# Controller.net
KiCad netlist of a schematic drawn in Altium Designer
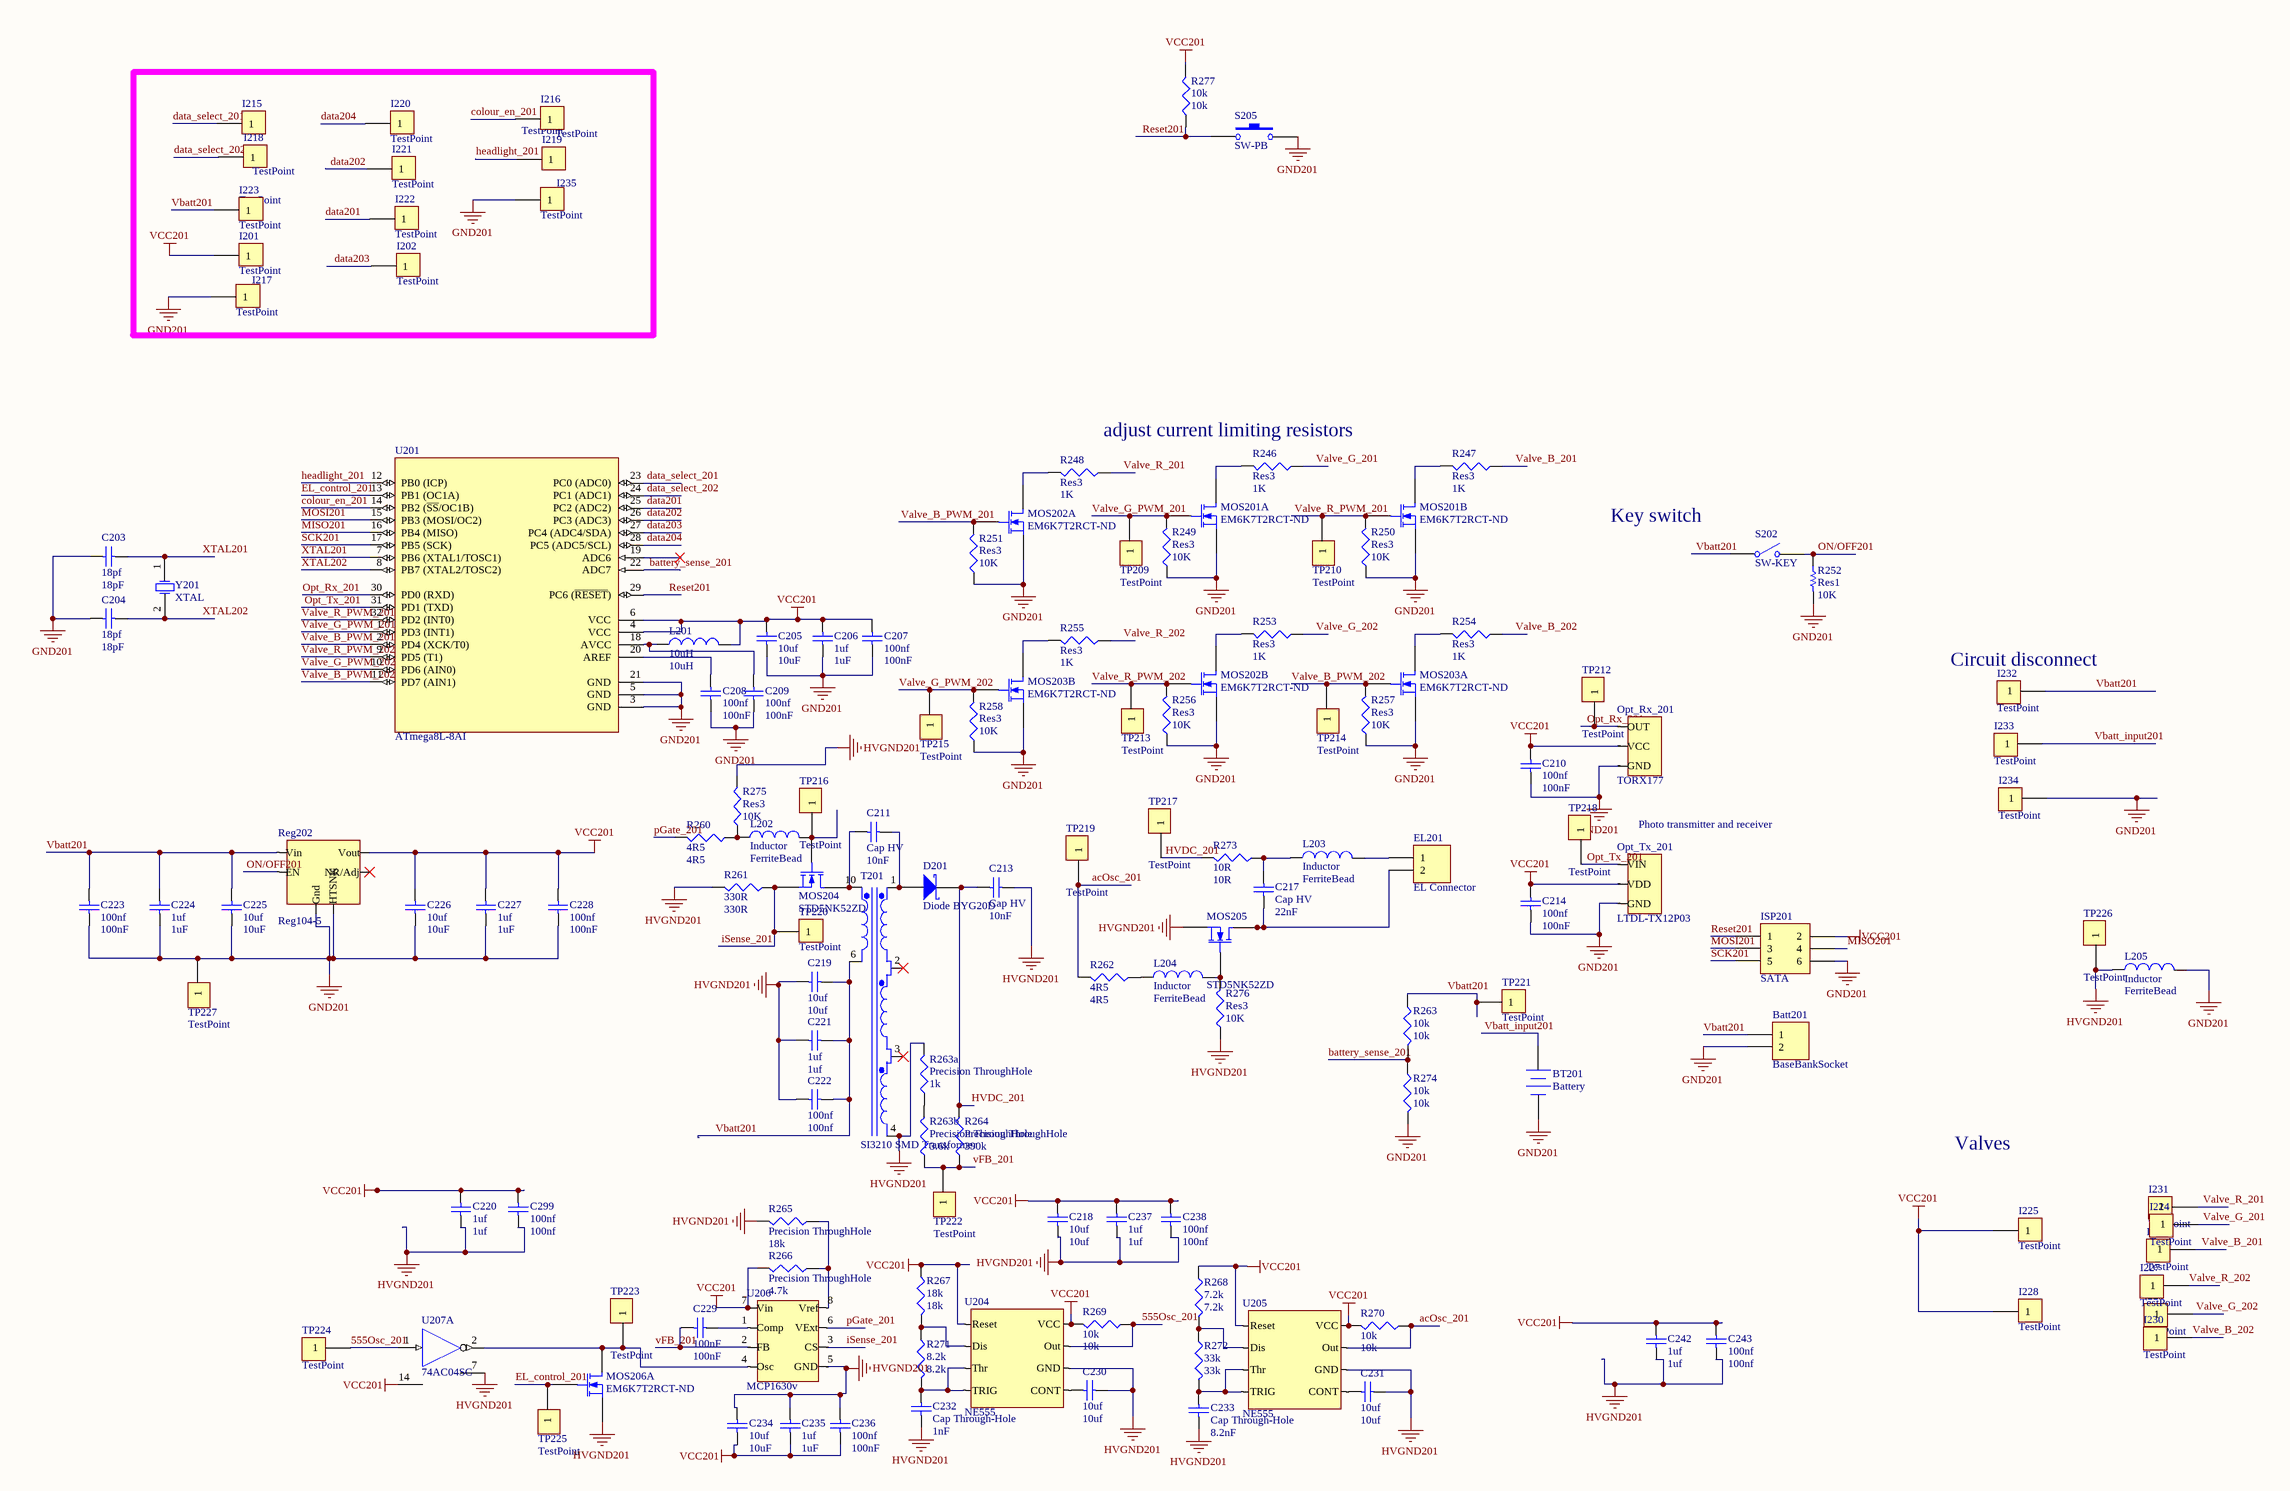
[diagram p0: Controller.SchDoc]

(export (version "E")
  (design (tool "Eeschema 10.0.6"))
  (components
    (comp (ref "Batt201")
      (value "BaseBankSocket")
      (footprint "HDR1X2")
      (description "Header, 2-Pin")
      (libsource (lib "Miscellaneous Connectors") (part "Header 2"))
    )
    (comp (ref "BT201")
      (value "Battery")
      (footprint "BAT-2")
      (description "Multicell Battery")
      (libsource (lib "Miscellaneous Devices") (part "Battery"))
    )
    (comp (ref "C203")
      (value "18pf")
      (footprint "0603")
      (description "Capacitor (Semiconductor SIM Model)")
      (fields (field (name "ALTIUM_VALUE") "18pF"))
      (libsource (lib "Miscellaneous Devices") (part "Cap Semi"))
    )
    (comp (ref "C204")
      (value "18pf")
      (footprint "0603")
      (description "Capacitor (Semiconductor SIM Model)")
      (fields (field (name "ALTIUM_VALUE") "18pF"))
      (libsource (lib "Miscellaneous Devices") (part "Cap Semi"))
    )
    (comp (ref "C205")
      (value "10uf")
      (footprint "0805")
      (description "Capacitor (Semiconductor SIM Model)")
      (fields (field (name "ALTIUM_VALUE") "10uF"))
      (libsource (lib "Miscellaneous Devices") (part "Cap Semi"))
    )
    (comp (ref "C206")
      (value "1uf")
      (footprint "0603")
      (description "Capacitor (Semiconductor SIM Model)")
      (fields (field (name "ALTIUM_VALUE") "1uF"))
      (libsource (lib "Miscellaneous Devices") (part "Cap Semi"))
    )
    (comp (ref "C207")
      (value "100nf")
      (footprint "0603")
      (description "Capacitor (Semiconductor SIM Model)")
      (fields (field (name "ALTIUM_VALUE") "100nF"))
      (libsource (lib "Miscellaneous Devices") (part "Cap Semi"))
    )
    (comp (ref "C208")
      (value "100nf")
      (footprint "0603")
      (description "Capacitor (Semiconductor SIM Model)")
      (fields (field (name "ALTIUM_VALUE") "100nF"))
      (libsource (lib "Miscellaneous Devices") (part "Cap Semi"))
    )
    (comp (ref "C209")
      (value "100nf")
      (footprint "0603")
      (description "Capacitor (Semiconductor SIM Model)")
      (fields (field (name "ALTIUM_VALUE") "100nF"))
      (libsource (lib "Miscellaneous Devices") (part "Cap Semi"))
    )
    (comp (ref "C210")
      (value "100nf")
      (footprint "0603")
      (description "Capacitor (Semiconductor SIM Model)")
      (fields (field (name "ALTIUM_VALUE") "100nF"))
      (libsource (lib "Miscellaneous Devices") (part "Cap Semi"))
    )
    (comp (ref "C211")
      (value "Cap HV")
      (footprint "10n MU Capacitor (HV)")
      (description "Capacitor (Semiconductor SIM Model)")
      (fields (field (name "ALTIUM_VALUE") "10nF"))
      (libsource (lib "Miscellaneous Devices") (part "Cap Semi"))
    )
    (comp (ref "C213")
      (value "Cap HV")
      (footprint "10n MU Capacitor (HV)")
      (description "Capacitor (Semiconductor SIM Model)")
      (fields (field (name "ALTIUM_VALUE") "10nF"))
      (libsource (lib "Miscellaneous Devices") (part "Cap Semi"))
    )
    (comp (ref "C214")
      (value "100nf")
      (footprint "0603")
      (description "Capacitor (Semiconductor SIM Model)")
      (fields (field (name "ALTIUM_VALUE") "100nF"))
      (libsource (lib "Miscellaneous Devices") (part "Cap Semi"))
    )
    (comp (ref "C217")
      (value "Cap HV")
      (footprint "22N MU Capacitor (HV)")
      (description "Capacitor (Semiconductor SIM Model)")
      (fields (field (name "ALTIUM_VALUE") "22nF"))
      (libsource (lib "Miscellaneous Devices") (part "Cap Semi"))
    )
    (comp (ref "C218")
      (value "10uf")
      (footprint "0805")
      (description "Capacitor (Semiconductor SIM Model)")
      (fields (field (name "ALTIUM_VALUE") "10uf"))
      (libsource (lib "Miscellaneous Devices") (part "Cap Semi"))
    )
    (comp (ref "C219")
      (value "10uf")
      (footprint "0805")
      (description "Capacitor (Semiconductor SIM Model)")
      (fields (field (name "ALTIUM_VALUE") "10uf"))
      (libsource (lib "Miscellaneous Devices") (part "Cap Semi"))
    )
    (comp (ref "C220")
      (value "1uf")
      (footprint "0603")
      (description "Capacitor (Semiconductor SIM Model)")
      (fields (field (name "ALTIUM_VALUE") "1uf"))
      (libsource (lib "Miscellaneous Devices") (part "Cap Semi"))
    )
    (comp (ref "C221")
      (value "1uf")
      (footprint "0603")
      (description "Capacitor (Semiconductor SIM Model)")
      (fields (field (name "ALTIUM_VALUE") "1uf"))
      (libsource (lib "Miscellaneous Devices") (part "Cap Semi"))
    )
    (comp (ref "C222")
      (value "100nf")
      (footprint "0603")
      (description "Capacitor (Semiconductor SIM Model)")
      (fields (field (name "ALTIUM_VALUE") "100nf"))
      (libsource (lib "Miscellaneous Devices") (part "Cap Semi"))
    )
    (comp (ref "C223")
      (value "100nf")
      (footprint "0603")
      (description "Capacitor (Semiconductor SIM Model)")
      (fields (field (name "ALTIUM_VALUE") "100nF"))
      (libsource (lib "Miscellaneous Devices") (part "Cap Semi"))
    )
    (comp (ref "C224")
      (value "1uf")
      (footprint "0603")
      (description "Capacitor (Semiconductor SIM Model)")
      (fields (field (name "ALTIUM_VALUE") "1uF"))
      (libsource (lib "Miscellaneous Devices") (part "Cap Semi"))
    )
    (comp (ref "C225")
      (value "10uf")
      (footprint "0805")
      (description "Capacitor (Semiconductor SIM Model)")
      (fields (field (name "ALTIUM_VALUE") "10uF"))
      (libsource (lib "Miscellaneous Devices") (part "Cap Semi"))
    )
    (comp (ref "C226")
      (value "10uf")
      (footprint "0805")
      (description "Capacitor (Semiconductor SIM Model)")
      (fields (field (name "ALTIUM_VALUE") "10uF"))
      (libsource (lib "Miscellaneous Devices") (part "Cap Semi"))
    )
    (comp (ref "C227")
      (value "1uf")
      (footprint "0603")
      (description "Capacitor (Semiconductor SIM Model)")
      (fields (field (name "ALTIUM_VALUE") "1uF"))
      (libsource (lib "Miscellaneous Devices") (part "Cap Semi"))
    )
    (comp (ref "C228")
      (value "100nf")
      (footprint "0603")
      (description "Capacitor (Semiconductor SIM Model)")
      (fields (field (name "ALTIUM_VALUE") "100nF"))
      (libsource (lib "Miscellaneous Devices") (part "Cap Semi"))
    )
    (comp (ref "C229")
      (value "100nF")
      (footprint "0603")
      (description "Capacitor (Semiconductor SIM Model)")
      (fields (field (name "ALTIUM_VALUE") "100nF"))
      (libsource (lib "Miscellaneous Devices") (part "Cap Semi"))
    )
    (comp (ref "C230")
      (value "10uf")
      (footprint "0805")
      (description "Capacitor (Semiconductor SIM Model)")
      (fields (field (name "ALTIUM_VALUE") "10uf"))
      (libsource (lib "Miscellaneous Devices") (part "Cap Semi"))
    )
    (comp (ref "C231")
      (value "10uf")
      (footprint "0805")
      (description "Capacitor (Semiconductor SIM Model)")
      (fields (field (name "ALTIUM_VALUE") "10uf"))
      (libsource (lib "Miscellaneous Devices") (part "Cap Semi"))
    )
    (comp (ref "C232")
      (value "Cap Through-Hole")
      (footprint "Axial 0.4 MU")
      (description "Capacitor (Semiconductor SIM Model)")
      (fields (field (name "ALTIUM_VALUE") "1nF"))
      (libsource (lib "Miscellaneous Devices") (part "Cap Semi"))
    )
    (comp (ref "C233")
      (value "Cap Through-Hole")
      (footprint "Axial 0.4 MU")
      (description "Capacitor (Semiconductor SIM Model)")
      (fields (field (name "ALTIUM_VALUE") "8.2nF"))
      (libsource (lib "Miscellaneous Devices") (part "Cap Semi"))
    )
    (comp (ref "C234")
      (value "10uf")
      (footprint "0805")
      (description "Capacitor (Semiconductor SIM Model)")
      (fields (field (name "ALTIUM_VALUE") "10uF"))
      (libsource (lib "Miscellaneous Devices") (part "Cap Semi"))
    )
    (comp (ref "C235")
      (value "1uf")
      (footprint "0603")
      (description "Capacitor (Semiconductor SIM Model)")
      (fields (field (name "ALTIUM_VALUE") "1uF"))
      (libsource (lib "Miscellaneous Devices") (part "Cap Semi"))
    )
    (comp (ref "C236")
      (value "100nf")
      (footprint "0603")
      (description "Capacitor (Semiconductor SIM Model)")
      (fields (field (name "ALTIUM_VALUE") "100nF"))
      (libsource (lib "Miscellaneous Devices") (part "Cap Semi"))
    )
    (comp (ref "C237")
      (value "1uf")
      (footprint "0603")
      (description "Capacitor (Semiconductor SIM Model)")
      (fields (field (name "ALTIUM_VALUE") "1uf"))
      (libsource (lib "Miscellaneous Devices") (part "Cap Semi"))
    )
    (comp (ref "C238")
      (value "100nf")
      (footprint "0603")
      (description "Capacitor (Semiconductor SIM Model)")
      (fields (field (name "ALTIUM_VALUE") "100nf"))
      (libsource (lib "Miscellaneous Devices") (part "Cap Semi"))
    )
    (comp (ref "C242")
      (value "1uf")
      (footprint "0603")
      (description "Capacitor (Semiconductor SIM Model)")
      (fields (field (name "ALTIUM_VALUE") "1uf"))
      (libsource (lib "Miscellaneous Devices") (part "Cap Semi"))
    )
    (comp (ref "C243")
      (value "100nf")
      (footprint "0603")
      (description "Capacitor (Semiconductor SIM Model)")
      (fields (field (name "ALTIUM_VALUE") "100nf"))
      (libsource (lib "Miscellaneous Devices") (part "Cap Semi"))
    )
    (comp (ref "C299")
      (value "100nf")
      (footprint "0603")
      (description "Capacitor (Semiconductor SIM Model)")
      (fields (field (name "ALTIUM_VALUE") "100nf"))
      (libsource (lib "Miscellaneous Devices") (part "Cap Semi"))
    )
    (comp (ref "D201")
      (value "Diode BYG20D")
      (footprint "BYG20J-E3")
      (description "Schottky Rectifier")
      (libsource (lib "Miscellaneous Devices") (part "Diode 10TQ035"))
    )
    (comp (ref "EL201")
      (value "EL Connector")
      (footprint "HV connector")
      (description "Header, 2-Pin")
      (libsource (lib "Miscellaneous Connectors") (part "Header 2"))
    )
    (comp (ref "I201") (value "TestPoint") (footprint "TestPoint") (libsource (lib "") (part "TestPoint_1")))
    (comp (ref "I202") (value "TestPoint") (footprint "TestPoint") (libsource (lib "") (part "TestPoint_1")))
    (comp (ref "I215") (value "TestPoint") (footprint "TestPoint") (libsource (lib "") (part "TestPoint_1")))
    (comp (ref "I216") (value "TestPoint") (footprint "TestPoint") (libsource (lib "") (part "TestPoint_1")))
    (comp (ref "I217") (value "TestPoint") (footprint "TestPoint") (libsource (lib "") (part "TestPoint_1")))
    (comp (ref "I218") (value "TestPoint") (footprint "TestPoint") (libsource (lib "") (part "TestPoint_1")))
    (comp (ref "I219") (value "TestPoint") (footprint "TestPoint") (libsource (lib "") (part "TestPoint_1")))
    (comp (ref "I220") (value "TestPoint") (footprint "TestPoint") (libsource (lib "") (part "TestPoint_1")))
    (comp (ref "I221") (value "TestPoint") (footprint "TestPoint") (libsource (lib "") (part "TestPoint_1")))
    (comp (ref "I222") (value "TestPoint") (footprint "TestPoint") (libsource (lib "") (part "TestPoint_1")))
    (comp (ref "I223") (value "TestPoint") (footprint "TestPoint") (libsource (lib "") (part "TestPoint_1")))
    (comp (ref "I224") (value "TestPoint") (footprint "TestPoint") (libsource (lib "") (part "TestPoint_2")))
    (comp (ref "I225") (value "TestPoint") (footprint "TestPoint") (libsource (lib "") (part "TestPoint_1")))
    (comp (ref "I226") (value "TestPoint") (footprint "TestPoint") (libsource (lib "") (part "TestPoint_2")))
    (comp (ref "I227") (value "TestPoint") (footprint "TestPoint") (libsource (lib "") (part "TestPoint_2")))
    (comp (ref "I228") (value "TestPoint") (footprint "TestPoint") (libsource (lib "") (part "TestPoint_1")))
    (comp (ref "I229") (value "TestPoint") (footprint "TestPoint") (libsource (lib "") (part "TestPoint_2")))
    (comp (ref "I230") (value "TestPoint") (footprint "TestPoint") (libsource (lib "") (part "TestPoint_2")))
    (comp (ref "I231") (value "TestPoint") (footprint "TestPoint") (libsource (lib "") (part "TestPoint_2")))
    (comp (ref "I232") (value "TestPoint") (footprint "TestPoint") (libsource (lib "") (part "TestPoint_2")))
    (comp (ref "I233") (value "TestPoint") (footprint "TestPoint") (libsource (lib "") (part "TestPoint_2")))
    (comp (ref "I234") (value "TestPoint") (footprint "TestPoint") (libsource (lib "") (part "TestPoint_2")))
    (comp (ref "I235") (value "TestPoint") (footprint "TestPoint") (libsource (lib "") (part "TestPoint_1")))
    (comp (ref "ISP201")
      (value "SATA")
      (footprint "SATA")
      (description "Header, 3-Pin, Dual row")
      (libsource (lib "Miscellaneous Connectors") (part "Header 3X2"))
    )
    (comp (ref "L201")
      (value "10uH")
      (footprint "0805")
      (description "Inductor")
      (fields (field (name "ALTIUM_VALUE") "10uH"))
      (libsource (lib "Miscellaneous Devices") (part "Inductor"))
    )
    (comp (ref "L202")
      (value "Inductor")
      (footprint "Axial 0.4 MU")
      (fields (field (name "ALTIUM_VALUE") "FerriteBead"))
      (libsource (lib "Miscellaneous Devices") (part "Inductor"))
    )
    (comp (ref "L203")
      (value "Inductor")
      (footprint "Axial 0.4 MU")
      (fields (field (name "ALTIUM_VALUE") "FerriteBead"))
      (libsource (lib "Miscellaneous Devices") (part "Inductor"))
    )
    (comp (ref "L204")
      (value "Inductor")
      (footprint "Axial 0.4 MU")
      (fields (field (name "ALTIUM_VALUE") "FerriteBead"))
      (libsource (lib "Miscellaneous Devices") (part "Inductor"))
    )
    (comp (ref "L205")
      (value "Inductor")
      (footprint "Axial 0.4 MU")
      (fields (field (name "ALTIUM_VALUE") "FerriteBead"))
      (libsource (lib "Miscellaneous Devices") (part "Inductor"))
    )
    (comp (ref "MOS201")
      (value "EM6K7T2RCT-ND")
      (footprint "EM6K7T2R-EMT6")
      (libsource (lib "Schlib1") (part "EM6K7T2RCT-ND"))
    )
    (comp (ref "MOS202")
      (value "EM6K7T2RCT-ND")
      (footprint "EM6K7T2R-EMT6")
      (libsource (lib "Schlib1") (part "EM6K7T2RCT-ND"))
    )
    (comp (ref "MOS203")
      (value "EM6K7T2RCT-ND")
      (footprint "EM6K7T2R-EMT6")
      (libsource (lib "Schlib1") (part "EM6K7T2RCT-ND"))
    )
    (comp (ref "MOS204")
      (value "STD5NK52ZD")
      (footprint "DPAK")
      (description "N-Channel MOSFET")
      (libsource (lib "Miscellaneous Devices") (part "MOSFET-N"))
    )
    (comp (ref "MOS205")
      (value "STD5NK52ZD")
      (footprint "DPAK")
      (description "N-Channel MOSFET")
      (libsource (lib "Miscellaneous Devices") (part "MOSFET-N"))
    )
    (comp (ref "MOS206")
      (value "EM6K7T2RCT-ND")
      (footprint "EM6K7T2R-EMT6")
      (libsource (lib "") (part "EM6K7T2RCT-ND_1"))
    )
    (comp (ref "Opt_Rx_201")
      (value "TORX177")
      (footprint "Optical RX")
      (description "Optical receiver module")
      (libsource (lib "Schlib1") (part "TORX177"))
    )
    (comp (ref "Opt_Tx_201")
      (value "LTDL-TX12P03")
      (footprint "Optical TX")
      (description "Optical transmitter")
      (libsource (lib "Schlib1") (part "LTDL-TX12P03"))
    )
    (comp (ref "R246")
      (value "Res3")
      (footprint "0805")
      (description "Resistor")
      (fields (field (name "ALTIUM_VALUE") "1K"))
      (libsource (lib "Miscellaneous Devices") (part "Res3"))
    )
    (comp (ref "R247")
      (value "Res3")
      (footprint "0805")
      (description "Resistor")
      (fields (field (name "ALTIUM_VALUE") "1K"))
      (libsource (lib "Miscellaneous Devices") (part "Res3"))
    )
    (comp (ref "R248")
      (value "Res3")
      (footprint "0805")
      (description "Resistor")
      (fields (field (name "ALTIUM_VALUE") "1K"))
      (libsource (lib "Miscellaneous Devices") (part "Res3"))
    )
    (comp (ref "R249")
      (value "Res3")
      (footprint "0805")
      (description "Resistor")
      (fields (field (name "ALTIUM_VALUE") "10K"))
      (libsource (lib "Miscellaneous Devices") (part "Res3"))
    )
    (comp (ref "R250")
      (value "Res3")
      (footprint "0805")
      (description "Resistor")
      (fields (field (name "ALTIUM_VALUE") "10K"))
      (libsource (lib "Miscellaneous Devices") (part "Res3"))
    )
    (comp (ref "R251")
      (value "Res3")
      (footprint "0805")
      (description "Resistor")
      (fields (field (name "ALTIUM_VALUE") "10K"))
      (libsource (lib "Miscellaneous Devices") (part "Res3"))
    )
    (comp (ref "R252")
      (value "Res1")
      (footprint "0805")
      (description "Resistor")
      (fields (field (name "ALTIUM_VALUE") "10K"))
      (libsource (lib "Miscellaneous Devices") (part "Res1"))
    )
    (comp (ref "R253")
      (value "Res3")
      (footprint "0805")
      (description "Resistor")
      (fields (field (name "ALTIUM_VALUE") "1K"))
      (libsource (lib "Miscellaneous Devices") (part "Res3"))
    )
    (comp (ref "R254")
      (value "Res3")
      (footprint "0805")
      (description "Resistor")
      (fields (field (name "ALTIUM_VALUE") "1K"))
      (libsource (lib "Miscellaneous Devices") (part "Res3"))
    )
    (comp (ref "R255")
      (value "Res3")
      (footprint "0805")
      (description "Resistor")
      (fields (field (name "ALTIUM_VALUE") "1K"))
      (libsource (lib "Miscellaneous Devices") (part "Res3"))
    )
    (comp (ref "R256")
      (value "Res3")
      (footprint "0805")
      (description "Resistor")
      (fields (field (name "ALTIUM_VALUE") "10K"))
      (libsource (lib "Miscellaneous Devices") (part "Res3"))
    )
    (comp (ref "R257")
      (value "Res3")
      (footprint "0805")
      (description "Resistor")
      (fields (field (name "ALTIUM_VALUE") "10K"))
      (libsource (lib "Miscellaneous Devices") (part "Res3"))
    )
    (comp (ref "R258")
      (value "Res3")
      (footprint "0805")
      (description "Resistor")
      (fields (field (name "ALTIUM_VALUE") "10K"))
      (libsource (lib "Miscellaneous Devices") (part "Res3"))
    )
    (comp (ref "R260")
      (value "4R5")
      (footprint "0805")
      (description "Resistor")
      (fields (field (name "ALTIUM_VALUE") "4R5"))
      (libsource (lib "Miscellaneous Devices") (part "Res3"))
    )
    (comp (ref "R261")
      (value "330R")
      (footprint "0805")
      (description "Resistor")
      (fields (field (name "ALTIUM_VALUE") "330R"))
      (libsource (lib "Miscellaneous Devices") (part "Res3"))
    )
    (comp (ref "R262")
      (value "4R5")
      (footprint "0805")
      (description "Resistor")
      (fields (field (name "ALTIUM_VALUE") "4R5"))
      (libsource (lib "Miscellaneous Devices") (part "Res3"))
    )
    (comp (ref "R263")
      (value "10k")
      (footprint "0603")
      (description "Resistor")
      (fields (field (name "ALTIUM_VALUE") "10k"))
      (libsource (lib "Miscellaneous Devices") (part "Res3"))
    )
    (comp (ref "R263a")
      (value "Precision ThroughHole")
      (footprint "Axial 0.4 MU")
      (description "Resistor")
      (fields (field (name "ALTIUM_VALUE") "1k"))
      (libsource (lib "Miscellaneous Devices") (part "Res3"))
    )
    (comp (ref "R263b")
      (value "Precision ThroughHole")
      (footprint "Axial 0.4 MU")
      (description "Resistor")
      (fields (field (name "ALTIUM_VALUE") "3.6k"))
      (libsource (lib "Miscellaneous Devices") (part "Res3"))
    )
    (comp (ref "R264")
      (value "Precision ThroughHole")
      (footprint "Axial 0.4 MU")
      (description "Resistor")
      (fields (field (name "ALTIUM_VALUE") "390k"))
      (libsource (lib "Miscellaneous Devices") (part "Res3"))
    )
    (comp (ref "R265")
      (value "Precision ThroughHole")
      (footprint "Axial 0.4 MU")
      (description "Resistor")
      (fields (field (name "ALTIUM_VALUE") "18k"))
      (libsource (lib "Miscellaneous Devices") (part "Res3"))
    )
    (comp (ref "R266")
      (value "Precision ThroughHole")
      (footprint "Axial 0.4 MU")
      (description "Resistor")
      (fields (field (name "ALTIUM_VALUE") "4.7k"))
      (libsource (lib "Miscellaneous Devices") (part "Res3"))
    )
    (comp (ref "R267")
      (value "18k")
      (footprint "0603")
      (description "Resistor")
      (fields (field (name "ALTIUM_VALUE") "18k"))
      (libsource (lib "Miscellaneous Devices") (part "Res3"))
    )
    (comp (ref "R268")
      (value "7.2k")
      (footprint "0805")
      (description "Resistor")
      (fields (field (name "ALTIUM_VALUE") "7.2k"))
      (libsource (lib "Miscellaneous Devices") (part "Res3"))
    )
    (comp (ref "R269")
      (value "10k")
      (footprint "0603")
      (description "Resistor")
      (fields (field (name "ALTIUM_VALUE") "10k"))
      (libsource (lib "Miscellaneous Devices") (part "Res3"))
    )
    (comp (ref "R270")
      (value "10k")
      (footprint "0603")
      (description "Resistor")
      (fields (field (name "ALTIUM_VALUE") "10k"))
      (libsource (lib "Miscellaneous Devices") (part "Res3"))
    )
    (comp (ref "R271")
      (value "8.2k")
      (footprint "0805")
      (description "Resistor")
      (fields (field (name "ALTIUM_VALUE") "8.2k"))
      (libsource (lib "Miscellaneous Devices") (part "Res3"))
    )
    (comp (ref "R272")
      (value "33k")
      (footprint "0805")
      (description "Resistor")
      (fields (field (name "ALTIUM_VALUE") "33k"))
      (libsource (lib "Miscellaneous Devices") (part "Res3"))
    )
    (comp (ref "R273")
      (value "10R")
      (footprint "0805")
      (description "Resistor")
      (fields (field (name "ALTIUM_VALUE") "10R"))
      (libsource (lib "Miscellaneous Devices") (part "Res3"))
    )
    (comp (ref "R274")
      (value "10k")
      (footprint "0603")
      (description "Resistor")
      (fields (field (name "ALTIUM_VALUE") "10k"))
      (libsource (lib "Miscellaneous Devices") (part "Res3"))
    )
    (comp (ref "R275")
      (value "Res3")
      (footprint "0805")
      (description "Resistor")
      (fields (field (name "ALTIUM_VALUE") "10K"))
      (libsource (lib "Miscellaneous Devices") (part "Res3"))
    )
    (comp (ref "R276")
      (value "Res3")
      (footprint "0805")
      (description "Resistor")
      (fields (field (name "ALTIUM_VALUE") "10K"))
      (libsource (lib "Miscellaneous Devices") (part "Res3"))
    )
    (comp (ref "R277")
      (value "10k")
      (footprint "0603")
      (description "Resistor")
      (fields (field (name "ALTIUM_VALUE") "10k"))
      (libsource (lib "Miscellaneous Devices") (part "Res3"))
    )
    (comp (ref "Reg202")
      (value "Reg104-5")
      (footprint "REG104-5-DDPAK5")
      (libsource (lib "Schlib1") (part "Reg104-5"))
    )
    (comp (ref "S202")
      (value "SW-KEY")
      (footprint "2 pin switch (surface mount)")
      (description "Single-Pole, Single-Throw Switch")
      (libsource (lib "Miscellaneous Devices") (part "SW-SPST"))
    )
    (comp (ref "S205")
      (value "SW-PB")
      (footprint "2 pin switch (surface mount)")
      (description "Switch")
      (libsource (lib "Miscellaneous Devices") (part "SW-PB"))
    )
    (comp (ref "T201")
      (value "SI3210 SMD Transformer")
      (footprint "SI3210 SMD Transformer")
      (libsource (lib "Schlib1") (part "SI3210 SMD Transformer"))
    )
    (comp (ref "TP209") (value "TestPoint") (footprint "TestPoint") (libsource (lib "") (part "TestPoint_3")))
    (comp (ref "TP210") (value "TestPoint") (footprint "TestPoint") (libsource (lib "") (part "TestPoint_3")))
    (comp (ref "TP212")
      (value "TestPoint")
      (footprint "TestPoint")
      (libsource (lib "Schlib1") (part "TestPoint"))
    )
    (comp (ref "TP213") (value "TestPoint") (footprint "TestPoint") (libsource (lib "") (part "TestPoint_3")))
    (comp (ref "TP214") (value "TestPoint") (footprint "TestPoint") (libsource (lib "") (part "TestPoint_3")))
    (comp (ref "TP215") (value "TestPoint") (footprint "TestPoint") (libsource (lib "") (part "TestPoint_3")))
    (comp (ref "TP216")
      (value "TestPoint")
      (footprint "TestPoint")
      (libsource (lib "Schlib1") (part "TestPoint"))
    )
    (comp (ref "TP217")
      (value "TestPoint")
      (footprint "TestPoint")
      (libsource (lib "Schlib1") (part "TestPoint"))
    )
    (comp (ref "TP218")
      (value "TestPoint")
      (footprint "TestPoint")
      (libsource (lib "Schlib1") (part "TestPoint"))
    )
    (comp (ref "TP219")
      (value "TestPoint")
      (footprint "TestPoint")
      (libsource (lib "Schlib1") (part "TestPoint"))
    )
    (comp (ref "TP220") (value "TestPoint") (footprint "TestPoint") (libsource (lib "") (part "TestPoint_1")))
    (comp (ref "TP221") (value "TestPoint") (footprint "TestPoint") (libsource (lib "") (part "TestPoint_1")))
    (comp (ref "TP222") (value "TestPoint") (footprint "TestPoint") (libsource (lib "") (part "TestPoint_3")))
    (comp (ref "TP223")
      (value "TestPoint")
      (footprint "TestPoint")
      (libsource (lib "Schlib1") (part "TestPoint"))
    )
    (comp (ref "TP224") (value "TestPoint") (footprint "TestPoint") (libsource (lib "") (part "TestPoint_2")))
    (comp (ref "TP225") (value "TestPoint") (footprint "TestPoint") (libsource (lib "") (part "TestPoint_3")))
    (comp (ref "TP226")
      (value "TestPoint")
      (footprint "TestPoint")
      (libsource (lib "Schlib1") (part "TestPoint"))
    )
    (comp (ref "TP227") (value "TestPoint") (footprint "TestPoint") (libsource (lib "") (part "TestPoint_3")))
    (comp (ref "U201")
      (value "ATmega8L-8AI")
      (footprint "ATMega_GOOD")
      (description "8-Bit AVR Microcontroller with 8K Bytes of In-System Programmable Flash Memory")
      (libsource (lib "Atmel Microcontroller 8-Bit AVR") (part "ATmega8L-8AI"))
    )
    (comp (ref "U204") (value "NE555") (footprint "NE555") (libsource (lib "Schlib1") (part "NE555")))
    (comp (ref "U205") (value "NE555") (footprint "NE555") (libsource (lib "Schlib1") (part "NE555")))
    (comp (ref "U206")
      (value "MCP1630v")
      (footprint "8MSOP (MCP Alternative)")
      (libsource (lib "Schlib1") (part "MCP1630v"))
    )
    (comp (ref "U207")
      (value "74AC04SC")
      (footprint "74AC04SC 14-SOIC")
      (description "Hex Inverter")
      (libsource (lib "TI Logic Gate 1") (part "SN54HC04J"))
    )
    (comp (ref "Y201")
      (value "XTAL")
      (footprint "ABLS-16MHz-B4-T")
      (description "Crystal Oscillator")
      (libsource (lib "Miscellaneous Devices") (part "XTAL"))
    )
  )
  (nets
    (net (code "1") (name "/555Osc_201") (class "Default")
      (node (ref "R269") (pin "1") (pinfunction "1_1") (pintype "passive"))
      (node (ref "TP224") (pin "1") (pinfunction "1_1") (pintype "passive"))
      (node (ref "U204") (pin "3") (pinfunction "Out_3") (pintype "passive"))
      (node (ref "U207") (pin "1") (pinfunction "A_1") (pintype "input"))
    )
    (net (code "2") (name "/EL_control_201") (class "Default")
      (node (ref "MOS206") (pin "2") (pinfunction "G_2") (pintype "passive"))
      (node (ref "TP225") (pin "1") (pinfunction "1_1") (pintype "passive"))
      (node (ref "U201") (pin "13") (pinfunction "PB1_(OC1A)_13") (pintype "bidirectional"))
    )
    (net (code "3") (name "/HVDC_201") (class "Default")
      (node (ref "C213") (pin "2") (pinfunction "2_2") (pintype "passive"))
      (node (ref "D201") (pin "1") (pinfunction "K_1") (pintype "passive"))
      (node (ref "R264") (pin "2") (pinfunction "2_2") (pintype "passive"))
      (node (ref "R273") (pin "1") (pinfunction "1_1") (pintype "passive"))
      (node (ref "TP217") (pin "1") (pinfunction "1_1") (pintype "passive"))
    )
    (net (code "4") (name "/MISO201") (class "Default")
      (node (ref "ISP201") (pin "4") (pinfunction "4_4") (pintype "passive"))
      (node (ref "U201") (pin "16") (pinfunction "PB4_(MISO)_16") (pintype "bidirectional"))
    )
    (net (code "5") (name "/MOSI201") (class "Default")
      (node (ref "ISP201") (pin "3") (pinfunction "3_3") (pintype "passive"))
      (node (ref "U201") (pin "15") (pinfunction "PB3_(MOSI/OC2)_15") (pintype "bidirectional"))
    )
    (net (code "6") (name "/ON{slash}OFF201") (class "Default")
      (node (ref "R252") (pin "1") (pinfunction "1_1") (pintype "passive"))
      (node (ref "Reg202") (pin "5") (pinfunction "EN_5") (pintype "passive"))
      (node (ref "S202") (pin "2") (pinfunction "NO_2") (pintype "passive"))
    )
    (net (code "7") (name "/Opt_Rx_201") (class "Default")
      (node (ref "Opt_Rx_201") (pin "1") (pinfunction "OUT_1") (pintype "passive"))
      (node (ref "TP212") (pin "1") (pinfunction "1_1") (pintype "passive"))
      (node (ref "U201") (pin "30") (pinfunction "PD0_(RXD)_30") (pintype "bidirectional"))
    )
    (net (code "8") (name "/Opt_Tx_201") (class "Default")
      (node (ref "Opt_Tx_201") (pin "1") (pinfunction "VIN_1") (pintype "passive"))
      (node (ref "TP218") (pin "1") (pinfunction "1_1") (pintype "passive"))
      (node (ref "U201") (pin "31") (pinfunction "PD1_(TXD)_31") (pintype "bidirectional"))
    )
    (net (code "9") (name "/Reset201") (class "Default")
      (node (ref "ISP201") (pin "1") (pinfunction "1_1") (pintype "passive"))
      (node (ref "R277") (pin "1") (pinfunction "1_1") (pintype "passive"))
      (node (ref "S205") (pin "1") (pinfunction "1_1") (pintype "passive"))
      (node (ref "U201") (pin "29") (pinfunction "PC6_(~{RESET})_29") (pintype "bidirectional"))
    )
    (net (code "10") (name "/SCK201") (class "Default")
      (node (ref "ISP201") (pin "5") (pinfunction "5_5") (pintype "passive"))
      (node (ref "U201") (pin "17") (pinfunction "PB5_(SCK)_17") (pintype "bidirectional"))
    )
    (net (code "11") (name "/Valve_B_201") (class "Default")
      (node (ref "I226") (pin "1") (pinfunction "1_1") (pintype "passive"))
      (node (ref "R247") (pin "1") (pinfunction "1_1") (pintype "passive"))
    )
    (net (code "12") (name "/Valve_B_202") (class "Default")
      (node (ref "I230") (pin "1") (pinfunction "1_1") (pintype "passive"))
      (node (ref "R254") (pin "1") (pinfunction "1_1") (pintype "passive"))
    )
    (net (code "13") (name "/Valve_B_PWM_201") (class "Default")
      (node (ref "MOS202") (pin "2") (pinfunction "G_2") (pintype "passive"))
      (node (ref "R251") (pin "2") (pinfunction "2_2") (pintype "passive"))
      (node (ref "U201") (pin "2") (pinfunction "PD4_(XCK/T0)_2") (pintype "bidirectional"))
    )
    (net (code "14") (name "/Valve_B_PWM_202") (class "Default")
      (node (ref "MOS203") (pin "2") (pinfunction "G_2") (pintype "passive"))
      (node (ref "R257") (pin "2") (pinfunction "2_2") (pintype "passive"))
      (node (ref "TP214") (pin "1") (pinfunction "1_1") (pintype "passive"))
      (node (ref "U201") (pin "11") (pinfunction "PD7_(AIN1)_11") (pintype "bidirectional"))
    )
    (net (code "15") (name "/Valve_G_201") (class "Default")
      (node (ref "I224") (pin "1") (pinfunction "1_1") (pintype "passive"))
      (node (ref "R246") (pin "1") (pinfunction "1_1") (pintype "passive"))
    )
    (net (code "16") (name "/Valve_G_202") (class "Default")
      (node (ref "I229") (pin "1") (pinfunction "1_1") (pintype "passive"))
      (node (ref "R253") (pin "1") (pinfunction "1_1") (pintype "passive"))
    )
    (net (code "17") (name "/Valve_G_PWM_201") (class "Default")
      (node (ref "MOS201") (pin "2") (pinfunction "G_2") (pintype "passive"))
      (node (ref "R249") (pin "2") (pinfunction "2_2") (pintype "passive"))
      (node (ref "TP209") (pin "1") (pinfunction "1_1") (pintype "passive"))
      (node (ref "U201") (pin "1") (pinfunction "PD3_(INT1)_1") (pintype "bidirectional"))
    )
    (net (code "18") (name "/Valve_G_PWM_202") (class "Default")
      (node (ref "MOS203") (pin "5") (pinfunction "G_5") (pintype "passive"))
      (node (ref "R258") (pin "2") (pinfunction "2_2") (pintype "passive"))
      (node (ref "TP215") (pin "1") (pinfunction "1_1") (pintype "passive"))
      (node (ref "U201") (pin "10") (pinfunction "PD6_(AIN0)_10") (pintype "bidirectional"))
    )
    (net (code "19") (name "/Valve_R_201") (class "Default")
      (node (ref "I231") (pin "1") (pinfunction "1_1") (pintype "passive"))
      (node (ref "R248") (pin "1") (pinfunction "1_1") (pintype "passive"))
    )
    (net (code "20") (name "/Valve_R_202") (class "Default")
      (node (ref "I227") (pin "1") (pinfunction "1_1") (pintype "passive"))
      (node (ref "R255") (pin "1") (pinfunction "1_1") (pintype "passive"))
    )
    (net (code "21") (name "/Valve_R_PWM_201") (class "Default")
      (node (ref "MOS201") (pin "5") (pinfunction "G_5") (pintype "passive"))
      (node (ref "R250") (pin "2") (pinfunction "2_2") (pintype "passive"))
      (node (ref "TP210") (pin "1") (pinfunction "1_1") (pintype "passive"))
      (node (ref "U201") (pin "32") (pinfunction "PD2_(INT0)_32") (pintype "bidirectional"))
    )
    (net (code "22") (name "/Valve_R_PWM_202") (class "Default")
      (node (ref "MOS202") (pin "5") (pinfunction "G_5") (pintype "passive"))
      (node (ref "R256") (pin "2") (pinfunction "2_2") (pintype "passive"))
      (node (ref "TP213") (pin "1") (pinfunction "1_1") (pintype "passive"))
      (node (ref "U201") (pin "9") (pinfunction "PD5_(T1)_9") (pintype "bidirectional"))
    )
    (net (code "23") (name "/Vbatt201") (class "Default")
      (node (ref "Batt201") (pin "1") (pinfunction "1_1") (pintype "passive"))
      (node (ref "C219") (pin "1") (pinfunction "1_1") (pintype "passive"))
      (node (ref "C221") (pin "1") (pinfunction "1_1") (pintype "passive"))
      (node (ref "C222") (pin "1") (pinfunction "1_1") (pintype "passive"))
      (node (ref "C223") (pin "2") (pinfunction "2_2") (pintype "passive"))
      (node (ref "C224") (pin "2") (pinfunction "2_2") (pintype "passive"))
      (node (ref "C225") (pin "2") (pinfunction "2_2") (pintype "passive"))
      (node (ref "I223") (pin "1") (pinfunction "1_1") (pintype "passive"))
      (node (ref "I232") (pin "1") (pinfunction "1_1") (pintype "passive"))
      (node (ref "R263") (pin "1") (pinfunction "1_1") (pintype "passive"))
      (node (ref "Reg202") (pin "1") (pinfunction "Vin_1") (pintype "passive"))
      (node (ref "S202") (pin "1") (pinfunction "COMMON_1") (pintype "passive"))
      (node (ref "T201") (pin "6") (pinfunction "Pri-_6") (pintype "passive"))
      (node (ref "TP221") (pin "1") (pinfunction "1_1") (pintype "passive"))
    )
    (net (code "24") (name "/Vbatt_input201") (class "Default")
      (node (ref "BT201") (pin "1") (pinfunction "+_1") (pintype "passive"))
      (node (ref "I233") (pin "1") (pinfunction "1_1") (pintype "passive"))
    )
    (net (code "25") (name "/XTAL201") (class "Default")
      (node (ref "C203") (pin "2") (pinfunction "2_2") (pintype "passive"))
      (node (ref "U201") (pin "7") (pinfunction "PB6_(XTAL1/TOSC1)_7") (pintype "bidirectional"))
      (node (ref "Y201") (pin "1") (pinfunction "OSC1_1") (pintype "passive"))
    )
    (net (code "26") (name "/XTAL202") (class "Default")
      (node (ref "C204") (pin "2") (pinfunction "2_2") (pintype "passive"))
      (node (ref "U201") (pin "8") (pinfunction "PB7_(XTAL2/TOSC2)_8") (pintype "bidirectional"))
      (node (ref "Y201") (pin "2") (pinfunction "OSC2_2") (pintype "passive"))
    )
    (net (code "27") (name "/acOsc_201") (class "Default")
      (node (ref "R262") (pin "2") (pinfunction "2_2") (pintype "passive"))
      (node (ref "R270") (pin "1") (pinfunction "1_1") (pintype "passive"))
      (node (ref "TP219") (pin "1") (pinfunction "1_1") (pintype "passive"))
      (node (ref "U205") (pin "3") (pinfunction "Out_3") (pintype "passive"))
    )
    (net (code "28") (name "/battery_sense_201") (class "Default")
      (node (ref "R263") (pin "2") (pinfunction "2_2") (pintype "passive"))
      (node (ref "R274") (pin "1") (pinfunction "1_1") (pintype "passive"))
      (node (ref "U201") (pin "22") (pinfunction "ADC7_22") (pintype "input"))
    )
    (net (code "29") (name "/colour_en_201") (class "Default")
      (node (ref "I216") (pin "1") (pinfunction "1_1") (pintype "passive"))
      (node (ref "U201") (pin "14") (pinfunction "PB2_(~{SS}/OC1B)_14") (pintype "bidirectional"))
    )
    (net (code "30") (name "/data201") (class "Default")
      (node (ref "I222") (pin "1") (pinfunction "1_1") (pintype "passive"))
      (node (ref "U201") (pin "25") (pinfunction "PC2_(ADC2)_25") (pintype "bidirectional"))
    )
    (net (code "31") (name "/data202") (class "Default")
      (node (ref "I221") (pin "1") (pinfunction "1_1") (pintype "passive"))
      (node (ref "U201") (pin "26") (pinfunction "PC3_(ADC3)_26") (pintype "bidirectional"))
    )
    (net (code "32") (name "/data203") (class "Default")
      (node (ref "I202") (pin "1") (pinfunction "1_1") (pintype "passive"))
      (node (ref "U201") (pin "27") (pinfunction "PC4_(ADC4/SDA)_27") (pintype "bidirectional"))
    )
    (net (code "33") (name "/data204") (class "Default")
      (node (ref "I220") (pin "1") (pinfunction "1_1") (pintype "passive"))
      (node (ref "U201") (pin "28") (pinfunction "PC5_(ADC5/SCL)_28") (pintype "bidirectional"))
    )
    (net (code "34") (name "/data_select_201") (class "Default")
      (node (ref "I215") (pin "1") (pinfunction "1_1") (pintype "passive"))
      (node (ref "U201") (pin "23") (pinfunction "PC0_(ADC0)_23") (pintype "bidirectional"))
    )
    (net (code "35") (name "/data_select_202") (class "Default")
      (node (ref "I218") (pin "1") (pinfunction "1_1") (pintype "passive"))
      (node (ref "U201") (pin "24") (pinfunction "PC1_(ADC1)_24") (pintype "bidirectional"))
    )
    (net (code "36") (name "/headlight_201") (class "Default")
      (node (ref "I219") (pin "1") (pinfunction "1_1") (pintype "passive"))
      (node (ref "U201") (pin "12") (pinfunction "PB0_(ICP)_12") (pintype "bidirectional"))
    )
    (net (code "37") (name "/iSense_201") (class "Default")
      (node (ref "MOS204") (pin "3") (pinfunction "S_3") (pintype "passive"))
      (node (ref "R261") (pin "1") (pinfunction "1_1") (pintype "passive"))
      (node (ref "TP220") (pin "1") (pinfunction "1_1") (pintype "passive"))
      (node (ref "U206") (pin "3") (pinfunction "CS_3") (pintype "passive"))
    )
    (net (code "38") (name "/pGate_201") (class "Default")
      (node (ref "R260") (pin "2") (pinfunction "2_2") (pintype "passive"))
      (node (ref "U206") (pin "6") (pinfunction "VExt_6") (pintype "passive"))
    )
    (net (code "39") (name "/vFB_201") (class "Default")
      (node (ref "C229") (pin "2") (pinfunction "2_2") (pintype "passive"))
      (node (ref "R263b") (pin "1") (pinfunction "1_1") (pintype "passive"))
      (node (ref "R264") (pin "1") (pinfunction "1_1") (pintype "passive"))
      (node (ref "TP222") (pin "1") (pinfunction "1_1") (pintype "passive"))
      (node (ref "U206") (pin "2") (pinfunction "FB_2") (pintype "passive"))
    )
    (net (code "40") (name "GND201") (class "Default")
      (node (ref "BT201") (pin "2") (pinfunction "-_2") (pintype "passive"))
      (node (ref "Batt201") (pin "2") (pinfunction "2_2") (pintype "passive"))
      (node (ref "C203") (pin "1") (pinfunction "1_1") (pintype "passive"))
      (node (ref "C204") (pin "1") (pinfunction "1_1") (pintype "passive"))
      (node (ref "C205") (pin "1") (pinfunction "1_1") (pintype "passive"))
      (node (ref "C206") (pin "1") (pinfunction "1_1") (pintype "passive"))
      (node (ref "C207") (pin "1") (pinfunction "1_1") (pintype "passive"))
      (node (ref "C208") (pin "1") (pinfunction "1_1") (pintype "passive"))
      (node (ref "C209") (pin "1") (pinfunction "1_1") (pintype "passive"))
      (node (ref "C210") (pin "1") (pinfunction "1_1") (pintype "passive"))
      (node (ref "C214") (pin "1") (pinfunction "1_1") (pintype "passive"))
      (node (ref "C223") (pin "1") (pinfunction "1_1") (pintype "passive"))
      (node (ref "C224") (pin "1") (pinfunction "1_1") (pintype "passive"))
      (node (ref "C225") (pin "1") (pinfunction "1_1") (pintype "passive"))
      (node (ref "C226") (pin "1") (pinfunction "1_1") (pintype "passive"))
      (node (ref "C227") (pin "1") (pinfunction "1_1") (pintype "passive"))
      (node (ref "C228") (pin "1") (pinfunction "1_1") (pintype "passive"))
      (node (ref "I217") (pin "1") (pinfunction "1_1") (pintype "passive"))
      (node (ref "I234") (pin "1") (pinfunction "1_1") (pintype "passive"))
      (node (ref "I235") (pin "1") (pinfunction "1_1") (pintype "passive"))
      (node (ref "ISP201") (pin "6") (pinfunction "6_6") (pintype "passive"))
      (node (ref "L205") (pin "2") (pinfunction "2_2") (pintype "passive"))
      (node (ref "MOS201") (pin "1") (pinfunction "S_1") (pintype "passive"))
      (node (ref "MOS201") (pin "4") (pinfunction "S_4") (pintype "passive"))
      (node (ref "MOS202") (pin "1") (pinfunction "S_1") (pintype "passive"))
      (node (ref "MOS202") (pin "4") (pinfunction "S_4") (pintype "passive"))
      (node (ref "MOS203") (pin "1") (pinfunction "S_1") (pintype "passive"))
      (node (ref "MOS203") (pin "4") (pinfunction "S_4") (pintype "passive"))
      (node (ref "Opt_Rx_201") (pin "2") (pinfunction "GND_2") (pintype "passive"))
      (node (ref "Opt_Tx_201") (pin "3") (pinfunction "GND_3") (pintype "passive"))
      (node (ref "R249") (pin "1") (pinfunction "1_1") (pintype "passive"))
      (node (ref "R250") (pin "1") (pinfunction "1_1") (pintype "passive"))
      (node (ref "R251") (pin "1") (pinfunction "1_1") (pintype "passive"))
      (node (ref "R252") (pin "2") (pinfunction "2_2") (pintype "passive"))
      (node (ref "R256") (pin "1") (pinfunction "1_1") (pintype "passive"))
      (node (ref "R257") (pin "1") (pinfunction "1_1") (pintype "passive"))
      (node (ref "R258") (pin "1") (pinfunction "1_1") (pintype "passive"))
      (node (ref "R274") (pin "2") (pinfunction "2_2") (pintype "passive"))
      (node (ref "Reg202") (pin "3") (pinfunction "Gnd_3") (pintype "passive"))
      (node (ref "Reg202") (pin "6") (pinfunction "HTSNK_6") (pintype "passive"))
      (node (ref "S205") (pin "2") (pinfunction "2_2") (pintype "passive"))
      (node (ref "TP227") (pin "1") (pinfunction "1_1") (pintype "passive"))
      (node (ref "U201") (pin "21") (pinfunction "GND_21") (pintype "power_in"))
      (node (ref "U201") (pin "3") (pinfunction "GND_3") (pintype "power_in"))
      (node (ref "U201") (pin "5") (pinfunction "GND_5") (pintype "power_in"))
    )
    (net (code "41") (name "HVGND201") (class "Default")
      (node (ref "C213") (pin "1") (pinfunction "1_1") (pintype "passive"))
      (node (ref "C218") (pin "2") (pinfunction "2_2") (pintype "passive"))
      (node (ref "C219") (pin "2") (pinfunction "2_2") (pintype "passive"))
      (node (ref "C220") (pin "2") (pinfunction "2_2") (pintype "passive"))
      (node (ref "C221") (pin "2") (pinfunction "2_2") (pintype "passive"))
      (node (ref "C222") (pin "2") (pinfunction "2_2") (pintype "passive"))
      (node (ref "C230") (pin "1") (pinfunction "1_1") (pintype "passive"))
      (node (ref "C231") (pin "1") (pinfunction "1_1") (pintype "passive"))
      (node (ref "C232") (pin "1") (pinfunction "1_1") (pintype "passive"))
      (node (ref "C233") (pin "1") (pinfunction "1_1") (pintype "passive"))
      (node (ref "C234") (pin "2") (pinfunction "2_2") (pintype "passive"))
      (node (ref "C235") (pin "2") (pinfunction "2_2") (pintype "passive"))
      (node (ref "C236") (pin "2") (pinfunction "2_2") (pintype "passive"))
      (node (ref "C237") (pin "2") (pinfunction "2_2") (pintype "passive"))
      (node (ref "C238") (pin "2") (pinfunction "2_2") (pintype "passive"))
      (node (ref "C242") (pin "2") (pinfunction "2_2") (pintype "passive"))
      (node (ref "C243") (pin "2") (pinfunction "2_2") (pintype "passive"))
      (node (ref "C299") (pin "2") (pinfunction "2_2") (pintype "passive"))
      (node (ref "L205") (pin "1") (pinfunction "1_1") (pintype "passive"))
      (node (ref "MOS205") (pin "3") (pinfunction "S_3") (pintype "passive"))
      (node (ref "MOS206") (pin "1") (pinfunction "S_1") (pintype "passive"))
      (node (ref "R261") (pin "2") (pinfunction "2_2") (pintype "passive"))
      (node (ref "R263a") (pin "2") (pinfunction "2_2") (pintype "passive"))
      (node (ref "R265") (pin "2") (pinfunction "2_2") (pintype "passive"))
      (node (ref "R275") (pin "2") (pinfunction "2_2") (pintype "passive"))
      (node (ref "R276") (pin "1") (pinfunction "1_1") (pintype "passive"))
      (node (ref "T201") (pin "4") (pinfunction "Sec3-_4") (pintype "passive"))
      (node (ref "TP226") (pin "1") (pinfunction "1_1") (pintype "passive"))
      (node (ref "U204") (pin "1") (pinfunction "GND_1") (pintype "passive"))
      (node (ref "U205") (pin "1") (pinfunction "GND_1") (pintype "passive"))
      (node (ref "U206") (pin "5") (pinfunction "GND_5") (pintype "passive"))
      (node (ref "U207") (pin "7") (pinfunction "GND_7") (pintype "power_in"))
    )
    (net (code "42") (name "Net-(C217-Pad2)") (class "Default")
      (node (ref "C217") (pin "2") (pinfunction "2_2") (pintype "passive"))
      (node (ref "L203") (pin "1") (pinfunction "1_1") (pintype "passive"))
      (node (ref "R273") (pin "2") (pinfunction "2_2") (pintype "passive"))
    )
    (net (code "43") (name "Net-(D201-A)") (class "Default")
      (node (ref "C211") (pin "1") (pinfunction "1_1") (pintype "passive"))
      (node (ref "D201") (pin "3") (pinfunction "A_3") (pintype "passive"))
      (node (ref "T201") (pin "1") (pinfunction "Sec1+_1") (pintype "passive"))
    )
    (net (code "44") (name "Net-(EL201-Pad1)") (class "Default")
      (node (ref "EL201") (pin "1") (pinfunction "1_1") (pintype "passive"))
      (node (ref "L203") (pin "2") (pinfunction "2_2") (pintype "passive"))
    )
    (net (code "45") (name "Net-(L202-Pad1)") (class "Default")
      (node (ref "L202") (pin "1") (pinfunction "1_1") (pintype "passive"))
      (node (ref "R260") (pin "1") (pinfunction "1_1") (pintype "passive"))
      (node (ref "R275") (pin "1") (pinfunction "1_1") (pintype "passive"))
    )
    (net (code "46") (name "Net-(L204-Pad1)") (class "Default")
      (node (ref "L204") (pin "1") (pinfunction "1_1") (pintype "passive"))
      (node (ref "R262") (pin "1") (pinfunction "1_1") (pintype "passive"))
    )
    (net (code "47") (name "Net-(MOS201A-D)") (class "Default")
      (node (ref "MOS201") (pin "6") (pinfunction "D_6") (pintype "passive"))
      (node (ref "R246") (pin "2") (pinfunction "2_2") (pintype "passive"))
    )
    (net (code "48") (name "Net-(MOS201B-D)") (class "Default")
      (node (ref "MOS201") (pin "3") (pinfunction "D_3") (pintype "passive"))
      (node (ref "R247") (pin "2") (pinfunction "2_2") (pintype "passive"))
    )
    (net (code "49") (name "Net-(MOS202A-D)") (class "Default")
      (node (ref "MOS202") (pin "6") (pinfunction "D_6") (pintype "passive"))
      (node (ref "R248") (pin "2") (pinfunction "2_2") (pintype "passive"))
    )
    (net (code "50") (name "Net-(MOS202B-D)") (class "Default")
      (node (ref "MOS202") (pin "3") (pinfunction "D_3") (pintype "passive"))
      (node (ref "R253") (pin "2") (pinfunction "2_2") (pintype "passive"))
    )
    (net (code "51") (name "Net-(MOS203A-D)") (class "Default")
      (node (ref "MOS203") (pin "6") (pinfunction "D_6") (pintype "passive"))
      (node (ref "R254") (pin "2") (pinfunction "2_2") (pintype "passive"))
    )
    (net (code "52") (name "Net-(MOS203B-D)") (class "Default")
      (node (ref "MOS203") (pin "3") (pinfunction "D_3") (pintype "passive"))
      (node (ref "R255") (pin "2") (pinfunction "2_2") (pintype "passive"))
    )
    (net (code "53") (name "Net-(MOS204-D)") (class "Default")
      (node (ref "C211") (pin "2") (pinfunction "2_2") (pintype "passive"))
      (node (ref "MOS204") (pin "1") (pinfunction "D_1") (pintype "passive"))
      (node (ref "T201") (pin "10") (pinfunction "Pri+_10") (pintype "passive"))
    )
    (net (code "54") (name "Net-(MOS204-G)") (class "Default")
      (node (ref "L202") (pin "2") (pinfunction "2_2") (pintype "passive"))
      (node (ref "MOS204") (pin "2") (pinfunction "G_2") (pintype "passive"))
      (node (ref "TP216") (pin "1") (pinfunction "1_1") (pintype "passive"))
    )
    (net (code "55") (name "Net-(MOS205-D)") (class "Default")
      (node (ref "C217") (pin "1") (pinfunction "1_1") (pintype "passive"))
      (node (ref "EL201") (pin "2") (pinfunction "2_2") (pintype "passive"))
      (node (ref "MOS205") (pin "1") (pinfunction "D_1") (pintype "passive"))
    )
    (net (code "56") (name "Net-(MOS205-G)") (class "Default")
      (node (ref "L204") (pin "2") (pinfunction "2_2") (pintype "passive"))
      (node (ref "MOS205") (pin "2") (pinfunction "G_2") (pintype "passive"))
      (node (ref "R276") (pin "2") (pinfunction "2_2") (pintype "passive"))
    )
    (net (code "57") (name "Net-(MOS206A-D)") (class "Default")
      (node (ref "MOS206") (pin "6") (pinfunction "D_6") (pintype "passive"))
      (node (ref "TP223") (pin "1") (pinfunction "1_1") (pintype "passive"))
      (node (ref "U206") (pin "4") (pinfunction "Osc_4") (pintype "passive"))
      (node (ref "U207") (pin "2") (pinfunction "Y_2") (pintype "output"))
    )
    (net (code "58") (name "Net-(R263a-Pad1)") (class "Default")
      (node (ref "R263a") (pin "1") (pinfunction "1_1") (pintype "passive"))
      (node (ref "R263b") (pin "2") (pinfunction "2_2") (pintype "passive"))
    )
    (net (code "59") (name "Net-(U201-AREF)") (class "Default")
      (node (ref "C208") (pin "2") (pinfunction "2_2") (pintype "passive"))
      (node (ref "U201") (pin "20") (pinfunction "AREF_20") (pintype "passive"))
    )
    (net (code "60") (name "Net-(U201-AVCC)") (class "Default")
      (node (ref "C209") (pin "2") (pinfunction "2_2") (pintype "passive"))
      (node (ref "L201") (pin "1") (pinfunction "1_1") (pintype "passive"))
      (node (ref "U201") (pin "18") (pinfunction "AVCC_18") (pintype "power_in"))
    )
    (net (code "61") (name "Net-(U204-CONT)") (class "Default")
      (node (ref "C230") (pin "2") (pinfunction "2_2") (pintype "passive"))
      (node (ref "U204") (pin "5") (pinfunction "CONT_5") (pintype "passive"))
    )
    (net (code "62") (name "Net-(U204-Dis)") (class "Default")
      (node (ref "R267") (pin "2") (pinfunction "2_2") (pintype "passive"))
      (node (ref "R271") (pin "1") (pinfunction "1_1") (pintype "passive"))
      (node (ref "U204") (pin "7") (pinfunction "Dis_7") (pintype "passive"))
    )
    (net (code "63") (name "Net-(U204-TRIG)") (class "Default")
      (node (ref "C232") (pin "2") (pinfunction "2_2") (pintype "passive"))
      (node (ref "R271") (pin "2") (pinfunction "2_2") (pintype "passive"))
      (node (ref "U204") (pin "2") (pinfunction "TRIG_2") (pintype "passive"))
      (node (ref "U204") (pin "6") (pinfunction "Thr_6") (pintype "passive"))
    )
    (net (code "64") (name "Net-(U205-CONT)") (class "Default")
      (node (ref "C231") (pin "2") (pinfunction "2_2") (pintype "passive"))
      (node (ref "U205") (pin "5") (pinfunction "CONT_5") (pintype "passive"))
    )
    (net (code "65") (name "Net-(U205-Dis)") (class "Default")
      (node (ref "R268") (pin "2") (pinfunction "2_2") (pintype "passive"))
      (node (ref "R272") (pin "1") (pinfunction "1_1") (pintype "passive"))
      (node (ref "U205") (pin "7") (pinfunction "Dis_7") (pintype "passive"))
    )
    (net (code "66") (name "Net-(U205-TRIG)") (class "Default")
      (node (ref "C233") (pin "2") (pinfunction "2_2") (pintype "passive"))
      (node (ref "R272") (pin "2") (pinfunction "2_2") (pintype "passive"))
      (node (ref "U205") (pin "2") (pinfunction "TRIG_2") (pintype "passive"))
      (node (ref "U205") (pin "6") (pinfunction "Thr_6") (pintype "passive"))
    )
    (net (code "67") (name "Net-(U206-Comp)") (class "Default")
      (node (ref "C229") (pin "1") (pinfunction "1_1") (pintype "passive"))
      (node (ref "U206") (pin "1") (pinfunction "Comp_1") (pintype "passive"))
    )
    (net (code "68") (name "Net-(U206-Vref)") (class "Default")
      (node (ref "R265") (pin "1") (pinfunction "1_1") (pintype "passive"))
      (node (ref "R266") (pin "1") (pinfunction "1_1") (pintype "passive"))
      (node (ref "U206") (pin "8") (pinfunction "Vref_8") (pintype "passive"))
    )
    (net (code "69") (name "VCC201") (class "Default")
      (node (ref "C205") (pin "2") (pinfunction "2_2") (pintype "passive"))
      (node (ref "C206") (pin "2") (pinfunction "2_2") (pintype "passive"))
      (node (ref "C207") (pin "2") (pinfunction "2_2") (pintype "passive"))
      (node (ref "C210") (pin "2") (pinfunction "2_2") (pintype "passive"))
      (node (ref "C214") (pin "2") (pinfunction "2_2") (pintype "passive"))
      (node (ref "C218") (pin "1") (pinfunction "1_1") (pintype "passive"))
      (node (ref "C220") (pin "1") (pinfunction "1_1") (pintype "passive"))
      (node (ref "C226") (pin "2") (pinfunction "2_2") (pintype "passive"))
      (node (ref "C227") (pin "2") (pinfunction "2_2") (pintype "passive"))
      (node (ref "C228") (pin "2") (pinfunction "2_2") (pintype "passive"))
      (node (ref "C234") (pin "1") (pinfunction "1_1") (pintype "passive"))
      (node (ref "C235") (pin "1") (pinfunction "1_1") (pintype "passive"))
      (node (ref "C236") (pin "1") (pinfunction "1_1") (pintype "passive"))
      (node (ref "C237") (pin "1") (pinfunction "1_1") (pintype "passive"))
      (node (ref "C238") (pin "1") (pinfunction "1_1") (pintype "passive"))
      (node (ref "C242") (pin "1") (pinfunction "1_1") (pintype "passive"))
      (node (ref "C243") (pin "1") (pinfunction "1_1") (pintype "passive"))
      (node (ref "C299") (pin "1") (pinfunction "1_1") (pintype "passive"))
      (node (ref "I201") (pin "1") (pinfunction "1_1") (pintype "passive"))
      (node (ref "I225") (pin "1") (pinfunction "1_1") (pintype "passive"))
      (node (ref "I228") (pin "1") (pinfunction "1_1") (pintype "passive"))
      (node (ref "ISP201") (pin "2") (pinfunction "2_2") (pintype "passive"))
      (node (ref "L201") (pin "2") (pinfunction "2_2") (pintype "passive"))
      (node (ref "Opt_Rx_201") (pin "3") (pinfunction "VCC_3") (pintype "passive"))
      (node (ref "Opt_Tx_201") (pin "2") (pinfunction "VDD_2") (pintype "passive"))
      (node (ref "R266") (pin "2") (pinfunction "2_2") (pintype "passive"))
      (node (ref "R267") (pin "1") (pinfunction "1_1") (pintype "passive"))
      (node (ref "R268") (pin "1") (pinfunction "1_1") (pintype "passive"))
      (node (ref "R269") (pin "2") (pinfunction "2_2") (pintype "passive"))
      (node (ref "R270") (pin "2") (pinfunction "2_2") (pintype "passive"))
      (node (ref "R277") (pin "2") (pinfunction "2_2") (pintype "passive"))
      (node (ref "Reg202") (pin "2") (pinfunction "Vout_2") (pintype "passive"))
      (node (ref "U201") (pin "4") (pinfunction "VCC_4") (pintype "power_in"))
      (node (ref "U201") (pin "6") (pinfunction "VCC_6") (pintype "power_in"))
      (node (ref "U204") (pin "4") (pinfunction "Reset_4") (pintype "passive"))
      (node (ref "U204") (pin "8") (pinfunction "VCC_8") (pintype "passive"))
      (node (ref "U205") (pin "4") (pinfunction "Reset_4") (pintype "passive"))
      (node (ref "U205") (pin "8") (pinfunction "VCC_8") (pintype "passive"))
      (node (ref "U206") (pin "7") (pinfunction "Vin_7") (pintype "passive"))
      (node (ref "U207") (pin "14") (pinfunction "VCC_14") (pintype "power_in"))
    )
    (net (code "70") (name "unconnected-(Reg202-NR{slash}Adj-Pad4)") (class "Default")
      (node (ref "Reg202") (pin "4") (pinfunction "NR/Adj_4") (pintype "passive+no_connect"))
    )
    (net (code "71") (name "unconnected-(T201-Sec2+-Pad2)") (class "Default")
      (node (ref "T201") (pin "2") (pinfunction "Sec2+_2") (pintype "passive+no_connect"))
    )
    (net (code "72") (name "unconnected-(T201-Sec3+-Pad3)") (class "Default")
      (node (ref "T201") (pin "3") (pinfunction "Sec3+_3") (pintype "passive+no_connect"))
    )
    (net (code "73") (name "unconnected-(U201-ADC6-Pad19)") (class "Default")
      (node (ref "U201") (pin "19") (pinfunction "ADC6_19") (pintype "input"))
    )
  )
)
